# demeter_v28-TSSOP.net
KiCad netlist of a schematic drawn in EAGLE
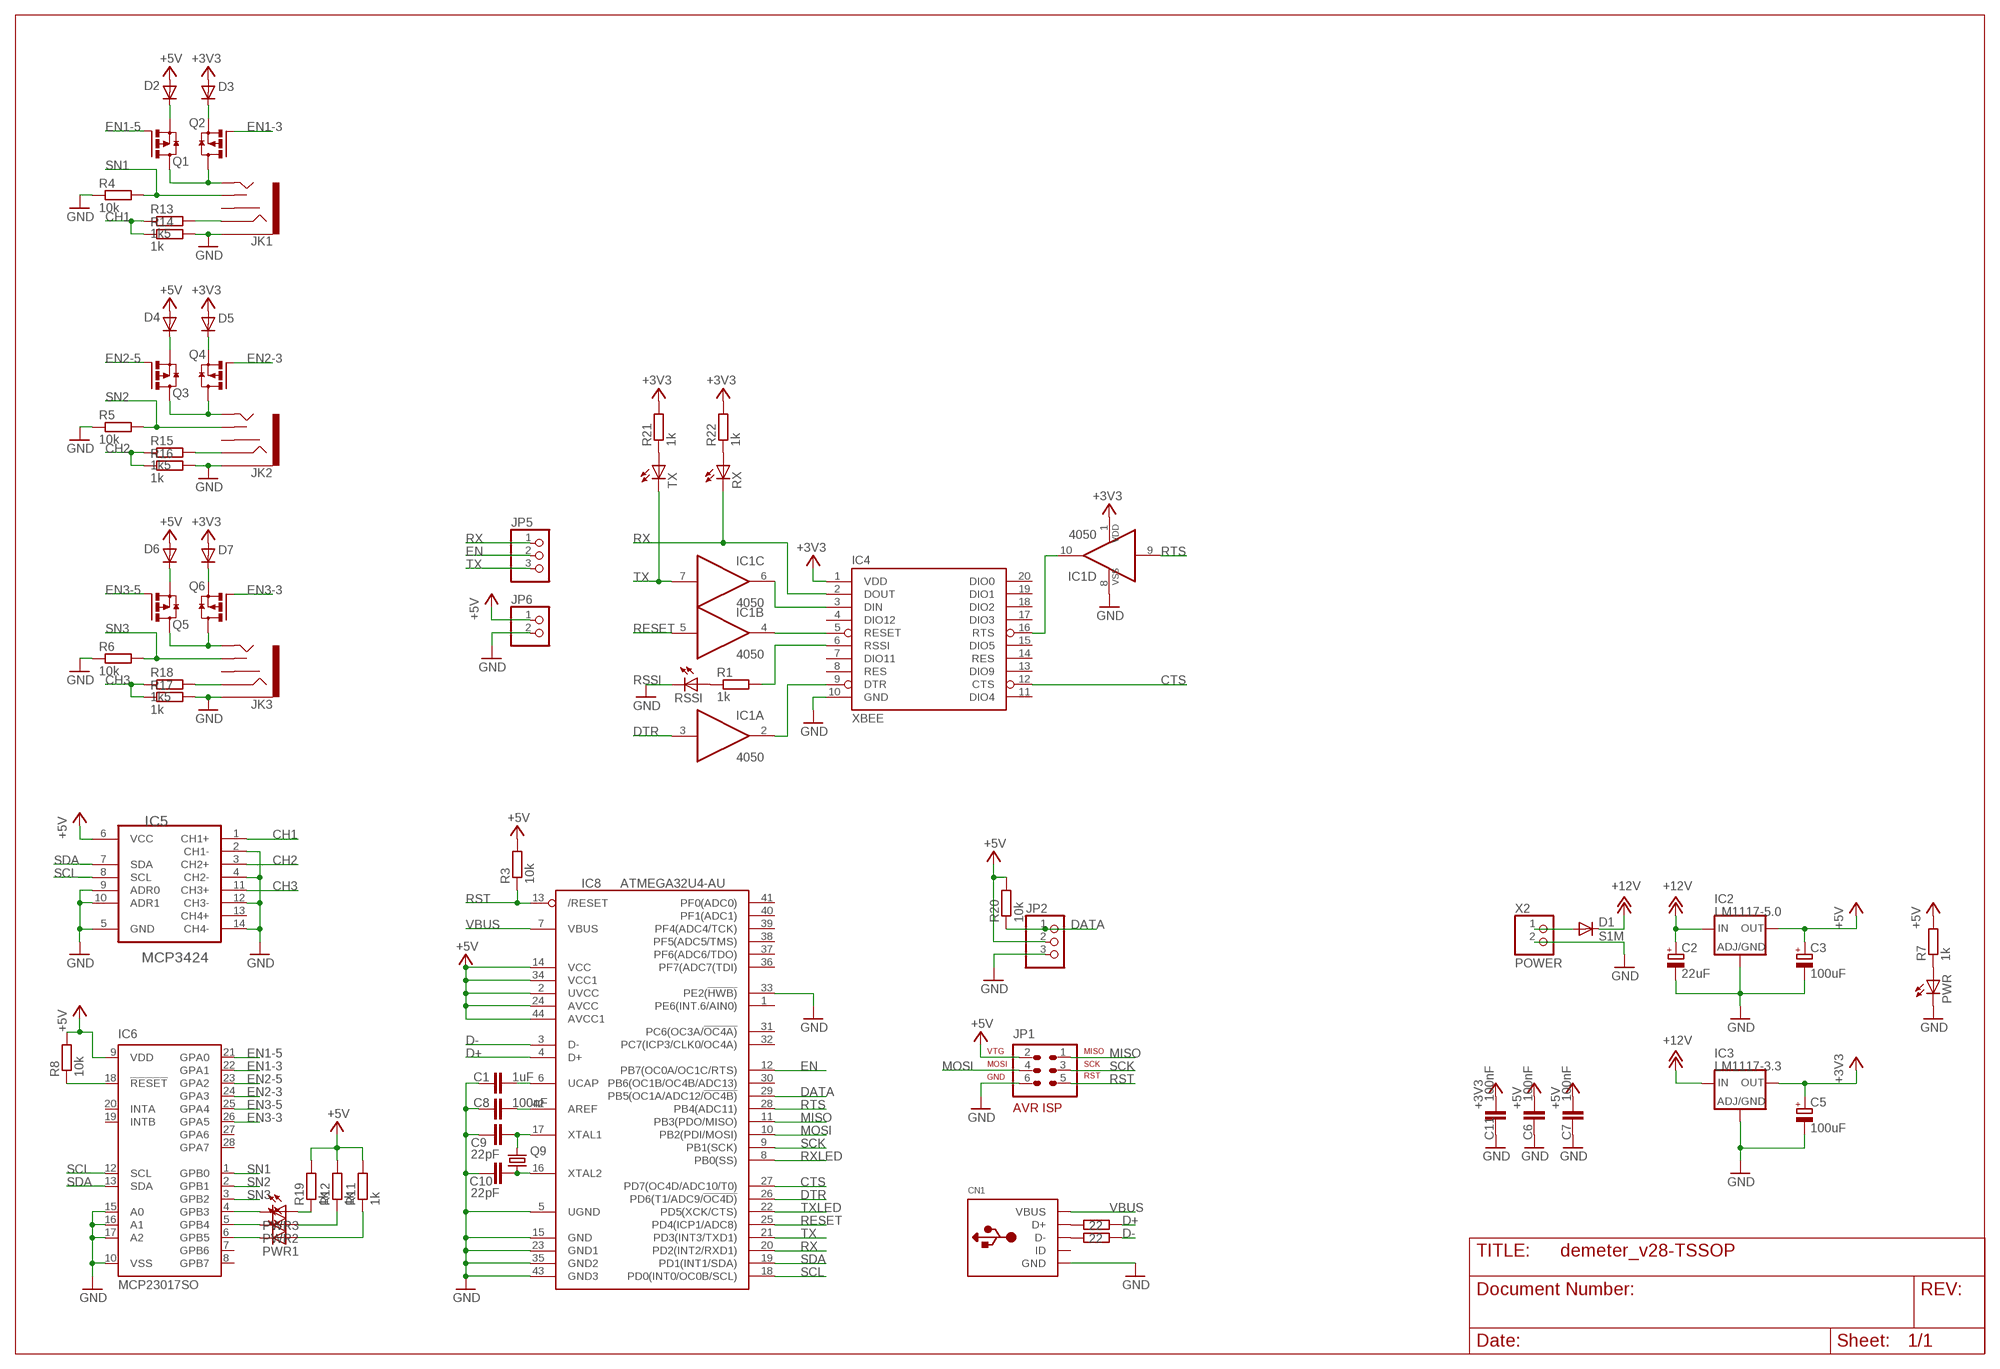
[diagram p0: schematic, sheet 1]

(export (version "E")
  (design (tool "Eeschema 10.0.6"))
  (components
    (comp (ref "C1")
      (value "1uF")
      (footprint "eagle-import:C0805K")
      (libsource (lib "eagle-import") (part "C-EUC0805K"))
    )
    (comp (ref "C2")
      (value "22uF")
      (footprint "eagle-import:PANASONIC_D")
      (libsource (lib "eagle-import") (part "CPOL-EUPD"))
    )
    (comp (ref "C3")
      (value "100uF")
      (footprint "eagle-import:PANASONIC_D")
      (libsource (lib "eagle-import") (part "CPOL-EUPD"))
    )
    (comp (ref "C5")
      (value "100uF")
      (footprint "eagle-import:PANASONIC_D")
      (libsource (lib "eagle-import") (part "CPOL-EUPD"))
    )
    (comp (ref "C6")
      (value "100nF")
      (footprint "eagle-import:C0805K")
      (libsource (lib "eagle-import") (part "C-EUC0805K"))
    )
    (comp (ref "C7")
      (value "100nF")
      (footprint "eagle-import:C0805K")
      (libsource (lib "eagle-import") (part "C-EUC0805K"))
    )
    (comp (ref "C8")
      (value "100nF")
      (footprint "eagle-import:C0805K")
      (libsource (lib "eagle-import") (part "C-EUC0805K"))
    )
    (comp (ref "C9")
      (value "22pF")
      (footprint "eagle-import:C0805K")
      (libsource (lib "eagle-import") (part "C-EUC0805K"))
    )
    (comp (ref "C10")
      (value "22pF")
      (footprint "eagle-import:C0805K")
      (libsource (lib "eagle-import") (part "C-EUC0805K"))
    )
    (comp (ref "C11")
      (value "100nF")
      (footprint "eagle-import:C0805K")
      (libsource (lib "eagle-import") (part "C-EUC0805K"))
    )
    (comp (ref "CN1")
      (value "USBMINIB")
      (footprint "eagle-import:USB-MINIB")
      (libsource (lib "eagle-import") (part "USBMINIB"))
    )
    (comp (ref "D1")
      (value "S1M")
      (footprint "eagle-import:DO-214AC")
      (libsource (lib "eagle-import") (part "S1M"))
    )
    (comp (ref "D2")
      (value "MBR0520")
      (footprint "eagle-import:SOD123")
      (libsource (lib "eagle-import") (part "MBR0520"))
    )
    (comp (ref "D3")
      (value "MBR0520")
      (footprint "eagle-import:SOD123")
      (libsource (lib "eagle-import") (part "MBR0520"))
    )
    (comp (ref "D4")
      (value "MBR0520")
      (footprint "eagle-import:SOD123")
      (libsource (lib "eagle-import") (part "MBR0520"))
    )
    (comp (ref "D5")
      (value "MBR0520")
      (footprint "eagle-import:SOD123")
      (libsource (lib "eagle-import") (part "MBR0520"))
    )
    (comp (ref "D6")
      (value "MBR0520")
      (footprint "eagle-import:SOD123")
      (libsource (lib "eagle-import") (part "MBR0520"))
    )
    (comp (ref "D7")
      (value "MBR0520")
      (footprint "eagle-import:SOD123")
      (libsource (lib "eagle-import") (part "MBR0520"))
    )
    (comp (ref "IC1")
      (value "4050")
      (footprint "eagle-import:SO16")
      (libsource (lib "eagle-import") (part "4050D"))
    )
    (comp (ref "IC2")
      (value "LM1117-5.0")
      (footprint "eagle-import:DPACK")
      (libsource (lib "eagle-import") (part "LM1117DT"))
    )
    (comp (ref "IC3")
      (value "LM1117-3.3")
      (footprint "eagle-import:DPACK")
      (libsource (lib "eagle-import") (part "LM1117DT"))
    )
    (comp (ref "IC4")
      (value "XBEE")
      (footprint "eagle-import:XBEE-1")
      (libsource (lib "eagle-import") (part "XBEE-1B1"))
    )
    (comp (ref "IC5")
      (value "MCP3424")
      (footprint "eagle-import:TSSOP14")
      (libsource (lib "eagle-import") (part "MCP3424T"))
    )
    (comp (ref "IC6")
      (value "MCP23017SO")
      (footprint "eagle-import:SO28W")
      (fields (field (name "MF") "MICROCHIP") (field (name "MPN") "MCP23017-E/SO"))
      (libsource (lib "eagle-import") (part "MCP23017SO"))
    )
    (comp (ref "IC8")
      (value "ATMEGA32U4-AU")
      (footprint "eagle-import:TQFP44")
      (libsource (lib "eagle-import") (part "ATMEGA32U4-AU"))
    )
    (comp (ref "JK1")
      (value "AUDIO-JACK2PTH")
      (footprint "eagle-import:AUDIO-JACK")
      (libsource (lib "eagle-import") (part "AUDIO-JACK2PTH"))
    )
    (comp (ref "JK2")
      (value "AUDIO-JACK2PTH")
      (footprint "eagle-import:AUDIO-JACK")
      (libsource (lib "eagle-import") (part "AUDIO-JACK2PTH"))
    )
    (comp (ref "JK3")
      (value "AUDIO-JACK2PTH")
      (footprint "eagle-import:AUDIO-JACK")
      (libsource (lib "eagle-import") (part "AUDIO-JACK2PTH"))
    )
    (comp (ref "JP1")
      (value "AVR-ISP")
      (footprint "eagle-import:AVR-ISP-6")
      (libsource (lib "eagle-import") (part "AVR-ISP-6"))
    )
    (comp (ref "JP2")
      (value "PINHD-1X3180")
      (footprint "eagle-import:1X03")
      (libsource (lib "eagle-import") (part "PINHD-1X3180"))
    )
    (comp (ref "JP5")
      (value "PINHD-1X3180")
      (footprint "eagle-import:1X03")
      (libsource (lib "eagle-import") (part "PINHD-1X3180"))
    )
    (comp (ref "JP6")
      (value "PINHD-1X2")
      (footprint "eagle-import:1X02")
      (libsource (lib "eagle-import") (part "PINHD-1X2"))
    )
    (comp (ref "PWR")
      (value "LED0805")
      (footprint "eagle-import:CHIP-LED0805")
      (libsource (lib "eagle-import") (part "LED0805"))
    )
    (comp (ref "PWR1")
      (value "LED0805")
      (footprint "eagle-import:CHIP-LED0805")
      (libsource (lib "eagle-import") (part "LED0805"))
    )
    (comp (ref "PWR2")
      (value "LED0805")
      (footprint "eagle-import:CHIP-LED0805")
      (libsource (lib "eagle-import") (part "LED0805"))
    )
    (comp (ref "PWR3")
      (value "LED0805")
      (footprint "eagle-import:CHIP-LED0805")
      (libsource (lib "eagle-import") (part "LED0805"))
    )
    (comp (ref "Q1")
      (value "IRLML6402")
      (footprint "eagle-import:SOT23")
      (libsource (lib "eagle-import") (part "IRLML6402"))
    )
    (comp (ref "Q2")
      (value "IRLML6402")
      (footprint "eagle-import:SOT23")
      (libsource (lib "eagle-import") (part "IRLML6402"))
    )
    (comp (ref "Q3")
      (value "IRLML6402")
      (footprint "eagle-import:SOT23")
      (libsource (lib "eagle-import") (part "IRLML6402"))
    )
    (comp (ref "Q4")
      (value "IRLML6402")
      (footprint "eagle-import:SOT23")
      (libsource (lib "eagle-import") (part "IRLML6402"))
    )
    (comp (ref "Q5")
      (value "IRLML6402")
      (footprint "eagle-import:SOT23")
      (libsource (lib "eagle-import") (part "IRLML6402"))
    )
    (comp (ref "Q6")
      (value "IRLML6402")
      (footprint "eagle-import:SOT23")
      (libsource (lib "eagle-import") (part "IRLML6402"))
    )
    (comp (ref "Q9")
      (value "CRYSTALHC49UP")
      (footprint "eagle-import:HC49UP")
      (libsource (lib "eagle-import") (part "CRYSTALHC49UP"))
    )
    (comp (ref "R1")
      (value "1k")
      (footprint "eagle-import:R0805")
      (libsource (lib "eagle-import") (part "R-EU_R0805"))
    )
    (comp (ref "R3")
      (value "10k")
      (footprint "eagle-import:R0805")
      (libsource (lib "eagle-import") (part "R-EU_R0805"))
    )
    (comp (ref "R4")
      (value "10k")
      (footprint "eagle-import:R0805")
      (libsource (lib "eagle-import") (part "R-EU_R0805"))
    )
    (comp (ref "R5")
      (value "10k")
      (footprint "eagle-import:R0805")
      (libsource (lib "eagle-import") (part "R-EU_R0805"))
    )
    (comp (ref "R6")
      (value "10k")
      (footprint "eagle-import:R0805")
      (libsource (lib "eagle-import") (part "R-EU_R0805"))
    )
    (comp (ref "R7")
      (value "1k")
      (footprint "eagle-import:R0805")
      (libsource (lib "eagle-import") (part "R-EU_R0805"))
    )
    (comp (ref "R8")
      (value "10k")
      (footprint "eagle-import:R0805")
      (libsource (lib "eagle-import") (part "R-EU_R0805"))
    )
    (comp (ref "R9")
      (value "22")
      (footprint "eagle-import:R0805")
      (libsource (lib "eagle-import") (part "R-EU_R0805"))
    )
    (comp (ref "R10")
      (value "22")
      (footprint "eagle-import:R0805")
      (libsource (lib "eagle-import") (part "R-EU_R0805"))
    )
    (comp (ref "R11")
      (value "1k")
      (footprint "eagle-import:R0805")
      (libsource (lib "eagle-import") (part "R-EU_R0805"))
    )
    (comp (ref "R12")
      (value "1k")
      (footprint "eagle-import:R0805")
      (libsource (lib "eagle-import") (part "R-EU_R0805"))
    )
    (comp (ref "R13")
      (value "1k5")
      (footprint "eagle-import:R0805")
      (libsource (lib "eagle-import") (part "R-EU_R0805"))
    )
    (comp (ref "R14")
      (value "1k")
      (footprint "eagle-import:R0805")
      (libsource (lib "eagle-import") (part "R-EU_R0805"))
    )
    (comp (ref "R15")
      (value "1k5")
      (footprint "eagle-import:R0805")
      (libsource (lib "eagle-import") (part "R-EU_R0805"))
    )
    (comp (ref "R16")
      (value "1k")
      (footprint "eagle-import:R0805")
      (libsource (lib "eagle-import") (part "R-EU_R0805"))
    )
    (comp (ref "R17")
      (value "1k")
      (footprint "eagle-import:R0805")
      (libsource (lib "eagle-import") (part "R-EU_R0805"))
    )
    (comp (ref "R18")
      (value "1k5")
      (footprint "eagle-import:R0805")
      (libsource (lib "eagle-import") (part "R-EU_R0805"))
    )
    (comp (ref "R19")
      (value "1k")
      (footprint "eagle-import:R0805")
      (libsource (lib "eagle-import") (part "R-EU_R0805"))
    )
    (comp (ref "R20")
      (value "10k")
      (footprint "eagle-import:R0805")
      (libsource (lib "eagle-import") (part "R-EU_R0805"))
    )
    (comp (ref "R21")
      (value "1k")
      (footprint "eagle-import:R0805")
      (libsource (lib "eagle-import") (part "R-EU_R0805"))
    )
    (comp (ref "R22")
      (value "1k")
      (footprint "eagle-import:R0805")
      (libsource (lib "eagle-import") (part "R-EU_R0805"))
    )
    (comp (ref "RSSI")
      (value "LED0805")
      (footprint "eagle-import:CHIP-LED0805")
      (libsource (lib "eagle-import") (part "LED0805"))
    )
    (comp (ref "RX")
      (value "LED0805")
      (footprint "eagle-import:CHIP-LED0805")
      (libsource (lib "eagle-import") (part "LED0805"))
    )
    (comp (ref "TX")
      (value "LED0805")
      (footprint "eagle-import:CHIP-LED0805")
      (libsource (lib "eagle-import") (part "LED0805"))
    )
    (comp (ref "X2")
      (value "POWER")
      (footprint "eagle-import:W237-102")
      (libsource (lib "eagle-import") (part "W237-102"))
    )
  )
  (nets
    (net (code "1") (name "+3V3") (class "Default")
      (node (ref "C11") (pin "1") (pinfunction "1_1") (pintype "passive"))
      (node (ref "C5") (pin "+") (pinfunction "+_+") (pintype "passive"))
      (node (ref "D3") (pin "A") (pinfunction "A_A") (pintype "passive"))
      (node (ref "D5") (pin "A") (pinfunction "A_A") (pintype "passive"))
      (node (ref "D7") (pin "A") (pinfunction "A_A") (pintype "passive"))
      (node (ref "IC1") (pin "1") (pinfunction "VDD_1") (pintype "power_in"))
      (node (ref "IC3") (pin "4") (pinfunction "OUT_4") (pintype "passive"))
      (node (ref "IC4") (pin "1") (pinfunction "VDD_1") (pintype "power_in"))
      (node (ref "R21") (pin "2") (pinfunction "2_2") (pintype "passive"))
      (node (ref "R22") (pin "2") (pinfunction "2_2") (pintype "passive"))
    )
    (net (code "2") (name "+5V") (class "Default")
      (node (ref "C3") (pin "+") (pinfunction "+_+") (pintype "passive"))
      (node (ref "C6") (pin "1") (pinfunction "1_1") (pintype "passive"))
      (node (ref "C7") (pin "1") (pinfunction "1_1") (pintype "passive"))
      (node (ref "D2") (pin "A") (pinfunction "A_A") (pintype "passive"))
      (node (ref "D4") (pin "A") (pinfunction "A_A") (pintype "passive"))
      (node (ref "D6") (pin "A") (pinfunction "A_A") (pintype "passive"))
      (node (ref "IC2") (pin "4") (pinfunction "OUT_4") (pintype "passive"))
      (node (ref "IC5") (pin "6") (pinfunction "VCC_6") (pintype "power_in"))
      (node (ref "IC6") (pin "9") (pinfunction "VDD_9") (pintype "power_in"))
      (node (ref "IC8") (pin "14") (pinfunction "VCC_14") (pintype "bidirectional"))
      (node (ref "IC8") (pin "2") (pinfunction "UVCC_2") (pintype "bidirectional"))
      (node (ref "IC8") (pin "24") (pinfunction "AVCC_24") (pintype "bidirectional"))
      (node (ref "IC8") (pin "34") (pinfunction "VCC1_34") (pintype "bidirectional"))
      (node (ref "IC8") (pin "44") (pinfunction "AVCC1_44") (pintype "bidirectional"))
      (node (ref "JP1") (pin "2") (pinfunction "VTG_2") (pintype "passive"))
      (node (ref "JP2") (pin "2") (pinfunction "2_2") (pintype "passive"))
      (node (ref "JP6") (pin "1") (pinfunction "1_1") (pintype "passive"))
      (node (ref "R11") (pin "2") (pinfunction "2_2") (pintype "passive"))
      (node (ref "R12") (pin "2") (pinfunction "2_2") (pintype "passive"))
      (node (ref "R19") (pin "2") (pinfunction "2_2") (pintype "passive"))
      (node (ref "R20") (pin "2") (pinfunction "2_2") (pintype "passive"))
      (node (ref "R3") (pin "2") (pinfunction "2_2") (pintype "passive"))
      (node (ref "R7") (pin "2") (pinfunction "2_2") (pintype "passive"))
      (node (ref "R8") (pin "2") (pinfunction "2_2") (pintype "passive"))
    )
    (net (code "3") (name "+12V") (class "Default")
      (node (ref "C2") (pin "+") (pinfunction "+_+") (pintype "passive"))
      (node (ref "D1") (pin "C") (pinfunction "C_C") (pintype "passive"))
      (node (ref "IC2") (pin "3") (pinfunction "IN_3") (pintype "input"))
      (node (ref "IC3") (pin "3") (pinfunction "IN_3") (pintype "input"))
    )
    (net (code "4") (name "/CH1") (class "Default")
      (node (ref "IC5") (pin "1") (pinfunction "CH1+_1") (pintype "input"))
      (node (ref "R13") (pin "1") (pinfunction "1_1") (pintype "passive"))
      (node (ref "R14") (pin "1") (pinfunction "1_1") (pintype "passive"))
    )
    (net (code "5") (name "/CH2") (class "Default")
      (node (ref "IC5") (pin "3") (pinfunction "CH2+_3") (pintype "input"))
      (node (ref "R15") (pin "1") (pinfunction "1_1") (pintype "passive"))
      (node (ref "R16") (pin "1") (pinfunction "1_1") (pintype "passive"))
    )
    (net (code "6") (name "/CH3") (class "Default")
      (node (ref "IC5") (pin "11") (pinfunction "CH3+_11") (pintype "input"))
      (node (ref "R17") (pin "1") (pinfunction "1_1") (pintype "passive"))
      (node (ref "R18") (pin "1") (pinfunction "1_1") (pintype "passive"))
    )
    (net (code "7") (name "/CTS") (class "Default")
      (node (ref "IC4") (pin "12") (pinfunction "CTS_12") (pintype "output"))
      (node (ref "IC8") (pin "27") (pinfunction "PD7(OC4D/ADC10/T0)_27") (pintype "bidirectional"))
    )
    (net (code "8") (name "/D+") (class "Default")
      (node (ref "IC8") (pin "4") (pinfunction "D+_4") (pintype "bidirectional"))
      (node (ref "R9") (pin "1") (pinfunction "1_1") (pintype "passive"))
    )
    (net (code "9") (name "/D-") (class "Default")
      (node (ref "IC8") (pin "3") (pinfunction "D-_3") (pintype "bidirectional"))
      (node (ref "R10") (pin "1") (pinfunction "1_1") (pintype "passive"))
    )
    (net (code "10") (name "/DATA") (class "Default")
      (node (ref "IC8") (pin "29") (pinfunction "PB5(OC1A/ADC12/~{OC4B})_29") (pintype "bidirectional"))
      (node (ref "JP2") (pin "1") (pinfunction "1_1") (pintype "passive"))
      (node (ref "R20") (pin "1") (pinfunction "1_1") (pintype "passive"))
    )
    (net (code "11") (name "/DTR") (class "Default")
      (node (ref "IC1") (pin "3") (pinfunction "I_3") (pintype "input"))
      (node (ref "IC8") (pin "26") (pinfunction "PD6(T1/ADC9/~{OC4D})_26") (pintype "bidirectional"))
    )
    (net (code "12") (name "/EN") (class "Default")
      (node (ref "IC8") (pin "12") (pinfunction "PB7(OC0A/OC1C/RTS)_12") (pintype "bidirectional"))
      (node (ref "JP5") (pin "2") (pinfunction "2_2") (pintype "passive"))
    )
    (net (code "13") (name "/EN1-3") (class "Default")
      (node (ref "IC6") (pin "22") (pinfunction "GPA1_22") (pintype "bidirectional"))
      (node (ref "Q2") (pin "1") (pinfunction "G_1") (pintype "passive"))
    )
    (net (code "14") (name "/EN1-5") (class "Default")
      (node (ref "IC6") (pin "21") (pinfunction "GPA0_21") (pintype "bidirectional"))
      (node (ref "Q1") (pin "1") (pinfunction "G_1") (pintype "passive"))
    )
    (net (code "15") (name "/EN2-3") (class "Default")
      (node (ref "IC6") (pin "24") (pinfunction "GPA3_24") (pintype "bidirectional"))
      (node (ref "Q4") (pin "1") (pinfunction "G_1") (pintype "passive"))
    )
    (net (code "16") (name "/EN2-5") (class "Default")
      (node (ref "IC6") (pin "23") (pinfunction "GPA2_23") (pintype "bidirectional"))
      (node (ref "Q3") (pin "1") (pinfunction "G_1") (pintype "passive"))
    )
    (net (code "17") (name "/EN3-3") (class "Default")
      (node (ref "IC6") (pin "26") (pinfunction "GPA5_26") (pintype "bidirectional"))
      (node (ref "Q6") (pin "1") (pinfunction "G_1") (pintype "passive"))
    )
    (net (code "18") (name "/EN3-5") (class "Default")
      (node (ref "IC6") (pin "25") (pinfunction "GPA4_25") (pintype "bidirectional"))
      (node (ref "Q5") (pin "1") (pinfunction "G_1") (pintype "passive"))
    )
    (net (code "19") (name "/MISO") (class "Default")
      (node (ref "IC8") (pin "11") (pinfunction "PB3(PDO/MISO)_11") (pintype "bidirectional"))
      (node (ref "JP1") (pin "1") (pinfunction "MISO_1") (pintype "passive"))
    )
    (net (code "20") (name "/MOSI") (class "Default")
      (node (ref "IC8") (pin "10") (pinfunction "PB2(PDI/MOSI)_10") (pintype "bidirectional"))
      (node (ref "JP1") (pin "4") (pinfunction "MOSI_4") (pintype "passive"))
    )
    (net (code "21") (name "/RESET") (class "Default")
      (node (ref "IC1") (pin "5") (pinfunction "I_5") (pintype "input"))
      (node (ref "IC8") (pin "25") (pinfunction "PD4(ICP1/ADC8)_25") (pintype "bidirectional"))
    )
    (net (code "22") (name "/RSSI") (class "Default")
      (node (ref "IC4") (pin "6") (pinfunction "RSSI_6") (pintype "bidirectional"))
      (node (ref "R1") (pin "2") (pinfunction "2_2") (pintype "passive"))
    )
    (net (code "23") (name "/RST") (class "Default")
      (node (ref "IC8") (pin "13") (pinfunction "/RESET_13") (pintype "bidirectional"))
      (node (ref "JP1") (pin "5") (pinfunction "RST_5") (pintype "passive"))
      (node (ref "R3") (pin "1") (pinfunction "1_1") (pintype "passive"))
    )
    (net (code "24") (name "/RTS") (class "Default")
      (node (ref "IC1") (pin "9") (pinfunction "I_9") (pintype "input"))
      (node (ref "IC8") (pin "28") (pinfunction "PB4(ADC11)_28") (pintype "bidirectional"))
    )
    (net (code "25") (name "/RX") (class "Default")
      (node (ref "IC4") (pin "2") (pinfunction "DOUT_2") (pintype "output"))
      (node (ref "IC8") (pin "20") (pinfunction "PD2(INT2/RXD1)_20") (pintype "bidirectional"))
      (node (ref "JP5") (pin "1") (pinfunction "1_1") (pintype "passive"))
      (node (ref "RX") (pin "C") (pinfunction "C_C") (pintype "passive"))
    )
    (net (code "26") (name "/RXLED") (class "Default")
      (node (ref "IC8") (pin "8") (pinfunction "PB0(SS)_8") (pintype "bidirectional"))
    )
    (net (code "27") (name "/SCK") (class "Default")
      (node (ref "IC8") (pin "9") (pinfunction "PB1(SCK)_9") (pintype "bidirectional"))
      (node (ref "JP1") (pin "3") (pinfunction "SCK_3") (pintype "passive"))
    )
    (net (code "28") (name "/SCL") (class "Default")
      (node (ref "IC5") (pin "8") (pinfunction "SCL_8") (pintype "input"))
      (node (ref "IC6") (pin "12") (pinfunction "SCL_12") (pintype "input"))
      (node (ref "IC8") (pin "18") (pinfunction "PD0(INT0/OC0B/SCL)_18") (pintype "bidirectional"))
    )
    (net (code "29") (name "/SDA") (class "Default")
      (node (ref "IC5") (pin "7") (pinfunction "SDA_7") (pintype "bidirectional"))
      (node (ref "IC6") (pin "13") (pinfunction "SDA_13") (pintype "bidirectional"))
      (node (ref "IC8") (pin "19") (pinfunction "PD1(INT1/SDA)_19") (pintype "bidirectional"))
    )
    (net (code "30") (name "/SN1") (class "Default")
      (node (ref "IC6") (pin "1") (pinfunction "GPB0_1") (pintype "bidirectional"))
      (node (ref "JK1") (pin "TSH") (pinfunction "TSH_TSH") (pintype "bidirectional"))
      (node (ref "R4") (pin "2") (pinfunction "2_2") (pintype "passive"))
    )
    (net (code "31") (name "/SN2") (class "Default")
      (node (ref "IC6") (pin "2") (pinfunction "GPB1_2") (pintype "bidirectional"))
      (node (ref "JK2") (pin "TSH") (pinfunction "TSH_TSH") (pintype "bidirectional"))
      (node (ref "R5") (pin "2") (pinfunction "2_2") (pintype "passive"))
    )
    (net (code "32") (name "/SN3") (class "Default")
      (node (ref "IC6") (pin "3") (pinfunction "GPB2_3") (pintype "bidirectional"))
      (node (ref "JK3") (pin "TSH") (pinfunction "TSH_TSH") (pintype "bidirectional"))
      (node (ref "R6") (pin "2") (pinfunction "2_2") (pintype "passive"))
    )
    (net (code "33") (name "/TX") (class "Default")
      (node (ref "IC1") (pin "7") (pinfunction "I_7") (pintype "input"))
      (node (ref "IC8") (pin "21") (pinfunction "PD3(INT3/TXD1)_21") (pintype "bidirectional"))
      (node (ref "JP5") (pin "3") (pinfunction "3_3") (pintype "passive"))
      (node (ref "TX") (pin "C") (pinfunction "C_C") (pintype "passive"))
    )
    (net (code "34") (name "/TXLED") (class "Default")
      (node (ref "IC8") (pin "22") (pinfunction "PD5(XCK/CTS)_22") (pintype "bidirectional"))
    )
    (net (code "35") (name "/VBUS") (class "Default")
      (node (ref "CN1") (pin "VBUS") (pinfunction "VBUS_VBUS") (pintype "power_in"))
      (node (ref "IC8") (pin "7") (pinfunction "VBUS_7") (pintype "bidirectional"))
    )
    (net (code "36") (name "GND") (class "Default")
      (node (ref "C1") (pin "2") (pinfunction "2_2") (pintype "passive"))
      (node (ref "C10") (pin "2") (pinfunction "2_2") (pintype "passive"))
      (node (ref "C11") (pin "2") (pinfunction "2_2") (pintype "passive"))
      (node (ref "C2") (pin "-") (pinfunction "-_-") (pintype "passive"))
      (node (ref "C3") (pin "-") (pinfunction "-_-") (pintype "passive"))
      (node (ref "C5") (pin "-") (pinfunction "-_-") (pintype "passive"))
      (node (ref "C6") (pin "2") (pinfunction "2_2") (pintype "passive"))
      (node (ref "C7") (pin "2") (pinfunction "2_2") (pintype "passive"))
      (node (ref "C8") (pin "2") (pinfunction "2_2") (pintype "passive"))
      (node (ref "C9") (pin "2") (pinfunction "2_2") (pintype "passive"))
      (node (ref "CN1") (pin "GND") (pinfunction "GND_GND") (pintype "power_in"))
      (node (ref "CN1") (pin "GND1") (pinfunction "GND_GND1") (pintype "power_in"))
      (node (ref "CN1") (pin "GND2") (pinfunction "GND_GND2") (pintype "power_in"))
      (node (ref "CN1") (pin "GND3") (pinfunction "GND_GND3") (pintype "power_in"))
      (node (ref "CN1") (pin "GND4") (pinfunction "GND_GND4") (pintype "power_in"))
      (node (ref "IC1") (pin "8") (pinfunction "VSS_8") (pintype "power_in"))
      (node (ref "IC2") (pin "1") (pinfunction "ADJ_1") (pintype "input"))
      (node (ref "IC3") (pin "1") (pinfunction "ADJ_1") (pintype "input"))
      (node (ref "IC4") (pin "10") (pinfunction "GND_10") (pintype "power_in"))
      (node (ref "IC5") (pin "10") (pinfunction "ADR1_10") (pintype "input"))
      (node (ref "IC5") (pin "12") (pinfunction "CH3-_12") (pintype "input"))
      (node (ref "IC5") (pin "14") (pinfunction "CH4-_14") (pintype "input"))
      (node (ref "IC5") (pin "2") (pinfunction "CH1-_2") (pintype "input"))
      (node (ref "IC5") (pin "4") (pinfunction "CH2-_4") (pintype "input"))
      (node (ref "IC5") (pin "5") (pinfunction "GND_5") (pintype "power_in"))
      (node (ref "IC5") (pin "9") (pinfunction "ADR0_9") (pintype "input"))
      (node (ref "IC6") (pin "10") (pinfunction "VSS_10") (pintype "power_in"))
      (node (ref "IC6") (pin "15") (pinfunction "A0_15") (pintype "input"))
      (node (ref "IC6") (pin "16") (pinfunction "A1_16") (pintype "input"))
      (node (ref "IC6") (pin "17") (pinfunction "A2_17") (pintype "input"))
      (node (ref "IC8") (pin "15") (pinfunction "GND_15") (pintype "bidirectional"))
      (node (ref "IC8") (pin "23") (pinfunction "GND1_23") (pintype "bidirectional"))
      (node (ref "IC8") (pin "33") (pinfunction "PE2(~{HWB})_33") (pintype "bidirectional"))
      (node (ref "IC8") (pin "35") (pinfunction "GND2_35") (pintype "bidirectional"))
      (node (ref "IC8") (pin "43") (pinfunction "GND3_43") (pintype "bidirectional"))
      (node (ref "IC8") (pin "5") (pinfunction "UGND_5") (pintype "bidirectional"))
      (node (ref "JK1") (pin "SLEEVE") (pinfunction "SLEEVE_SLEEVE") (pintype "bidirectional"))
      (node (ref "JK2") (pin "SLEEVE") (pinfunction "SLEEVE_SLEEVE") (pintype "bidirectional"))
      (node (ref "JK3") (pin "SLEEVE") (pinfunction "SLEEVE_SLEEVE") (pintype "bidirectional"))
      (node (ref "JP1") (pin "6") (pinfunction "GND_6") (pintype "passive"))
      (node (ref "JP2") (pin "3") (pinfunction "3_3") (pintype "passive"))
      (node (ref "JP6") (pin "2") (pinfunction "2_2") (pintype "passive"))
      (node (ref "PWR") (pin "C") (pinfunction "C_C") (pintype "passive"))
      (node (ref "R14") (pin "2") (pinfunction "2_2") (pintype "passive"))
      (node (ref "R16") (pin "2") (pinfunction "2_2") (pintype "passive"))
      (node (ref "R17") (pin "2") (pinfunction "2_2") (pintype "passive"))
      (node (ref "R4") (pin "1") (pinfunction "1_1") (pintype "passive"))
      (node (ref "R5") (pin "1") (pinfunction "1_1") (pintype "passive"))
      (node (ref "R6") (pin "1") (pinfunction "1_1") (pintype "passive"))
      (node (ref "RSSI") (pin "C") (pinfunction "C_C") (pintype "passive"))
      (node (ref "X2") (pin "2") (pinfunction "2_2") (pintype "passive"))
    )
    (net (code "37") (name "Net-(CN1-PadD+)") (class "Default")
      (node (ref "CN1") (pin "D+") (pinfunction "D+_D+") (pintype "bidirectional"))
      (node (ref "R9") (pin "2") (pinfunction "2_2") (pintype "passive"))
    )
    (net (code "38") (name "Net-(CN1-PadD-)") (class "Default")
      (node (ref "CN1") (pin "D-") (pinfunction "D-_D-") (pintype "bidirectional"))
      (node (ref "R10") (pin "2") (pinfunction "2_2") (pintype "passive"))
    )
    (net (code "39") (name "Net-(D1-PadA)") (class "Default")
      (node (ref "D1") (pin "A") (pinfunction "A_A") (pintype "passive"))
      (node (ref "X2") (pin "1") (pinfunction "1_1") (pintype "passive"))
    )
    (net (code "40") (name "Net-(IC1A-O)") (class "Default")
      (node (ref "IC1") (pin "2") (pinfunction "O_2") (pintype "output"))
      (node (ref "IC4") (pin "9") (pinfunction "DTR_9") (pintype "bidirectional"))
    )
    (net (code "41") (name "Net-(IC1B-O)") (class "Default")
      (node (ref "IC1") (pin "4") (pinfunction "O_4") (pintype "output"))
      (node (ref "IC4") (pin "5") (pinfunction "RESET_5") (pintype "input"))
    )
    (net (code "42") (name "Net-(IC1C-O)") (class "Default")
      (node (ref "IC1") (pin "6") (pinfunction "O_6") (pintype "output"))
      (node (ref "IC4") (pin "3") (pinfunction "DIN_3") (pintype "input"))
    )
    (net (code "43") (name "Net-(IC1D-O)") (class "Default")
      (node (ref "IC1") (pin "10") (pinfunction "O_10") (pintype "output"))
      (node (ref "IC4") (pin "16") (pinfunction "RTS_16") (pintype "input"))
    )
    (net (code "44") (name "Net-(IC6-GPB3)") (class "Default")
      (node (ref "IC6") (pin "4") (pinfunction "GPB3_4") (pintype "bidirectional"))
      (node (ref "PWR3") (pin "C") (pinfunction "C_C") (pintype "passive"))
    )
    (net (code "45") (name "Net-(IC6-GPB4)") (class "Default")
      (node (ref "IC6") (pin "5") (pinfunction "GPB4_5") (pintype "bidirectional"))
      (node (ref "PWR2") (pin "C") (pinfunction "C_C") (pintype "passive"))
    )
    (net (code "46") (name "Net-(IC6-GPB5)") (class "Default")
      (node (ref "IC6") (pin "6") (pinfunction "GPB5_6") (pintype "bidirectional"))
      (node (ref "PWR1") (pin "C") (pinfunction "C_C") (pintype "passive"))
    )
    (net (code "47") (name "Net-(IC6-~{RESET})") (class "Default")
      (node (ref "IC6") (pin "18") (pinfunction "~{RESET}_18") (pintype "input"))
      (node (ref "R8") (pin "1") (pinfunction "1_1") (pintype "passive"))
    )
    (net (code "48") (name "Net-(IC8-AREF)") (class "Default")
      (node (ref "C8") (pin "1") (pinfunction "1_1") (pintype "passive"))
      (node (ref "IC8") (pin "42") (pinfunction "AREF_42") (pintype "bidirectional"))
    )
    (net (code "49") (name "Net-(IC8-UCAP)") (class "Default")
      (node (ref "C1") (pin "1") (pinfunction "1_1") (pintype "passive"))
      (node (ref "IC8") (pin "6") (pinfunction "UCAP_6") (pintype "bidirectional"))
    )
    (net (code "50") (name "Net-(IC8-XTAL1)") (class "Default")
      (node (ref "C9") (pin "1") (pinfunction "1_1") (pintype "passive"))
      (node (ref "IC8") (pin "17") (pinfunction "XTAL1_17") (pintype "bidirectional"))
      (node (ref "Q9") (pin "2") (pinfunction "2_2") (pintype "passive"))
    )
    (net (code "51") (name "Net-(IC8-XTAL2)") (class "Default")
      (node (ref "C10") (pin "1") (pinfunction "1_1") (pintype "passive"))
      (node (ref "IC8") (pin "16") (pinfunction "XTAL2_16") (pintype "bidirectional"))
      (node (ref "Q9") (pin "1") (pinfunction "1_1") (pintype "passive"))
    )
    (net (code "52") (name "Net-(JK1-PadRING)") (class "Default")
      (node (ref "JK1") (pin "RING") (pinfunction "RING_RING") (pintype "bidirectional"))
      (node (ref "R13") (pin "2") (pinfunction "2_2") (pintype "passive"))
    )
    (net (code "53") (name "Net-(JK2-PadRING)") (class "Default")
      (node (ref "JK2") (pin "RING") (pinfunction "RING_RING") (pintype "bidirectional"))
      (node (ref "R15") (pin "2") (pinfunction "2_2") (pintype "passive"))
    )
    (net (code "54") (name "Net-(JK3-PadRING)") (class "Default")
      (node (ref "JK3") (pin "RING") (pinfunction "RING_RING") (pintype "bidirectional"))
      (node (ref "R18") (pin "2") (pinfunction "2_2") (pintype "passive"))
    )
    (net (code "55") (name "Net-(PWR-PadA)") (class "Default")
      (node (ref "PWR") (pin "A") (pinfunction "A_A") (pintype "passive"))
      (node (ref "R7") (pin "1") (pinfunction "1_1") (pintype "passive"))
    )
    (net (code "56") (name "Net-(PWR1-PadA)") (class "Default")
      (node (ref "PWR1") (pin "A") (pinfunction "A_A") (pintype "passive"))
      (node (ref "R11") (pin "1") (pinfunction "1_1") (pintype "passive"))
    )
    (net (code "57") (name "Net-(PWR2-PadA)") (class "Default")
      (node (ref "PWR2") (pin "A") (pinfunction "A_A") (pintype "passive"))
      (node (ref "R12") (pin "1") (pinfunction "1_1") (pintype "passive"))
    )
    (net (code "58") (name "Net-(PWR3-PadA)") (class "Default")
      (node (ref "PWR3") (pin "A") (pinfunction "A_A") (pintype "passive"))
      (node (ref "R19") (pin "1") (pinfunction "1_1") (pintype "passive"))
    )
    (net (code "59") (name "Net-(Q1-D)") (class "Default")
      (node (ref "JK1") (pin "TIP") (pinfunction "TIP_TIP") (pintype "bidirectional"))
      (node (ref "Q1") (pin "3") (pinfunction "D_3") (pintype "passive"))
      (node (ref "Q2") (pin "3") (pinfunction "D_3") (pintype "passive"))
    )
    (net (code "60") (name "Net-(Q1-S)") (class "Default")
      (node (ref "D2") (pin "C") (pinfunction "C_C") (pintype "passive"))
      (node (ref "Q1") (pin "2") (pinfunction "S_2") (pintype "passive"))
    )
    (net (code "61") (name "Net-(Q2-S)") (class "Default")
      (node (ref "D3") (pin "C") (pinfunction "C_C") (pintype "passive"))
      (node (ref "Q2") (pin "2") (pinfunction "S_2") (pintype "passive"))
    )
    (net (code "62") (name "Net-(Q3-D)") (class "Default")
      (node (ref "JK2") (pin "TIP") (pinfunction "TIP_TIP") (pintype "bidirectional"))
      (node (ref "Q3") (pin "3") (pinfunction "D_3") (pintype "passive"))
      (node (ref "Q4") (pin "3") (pinfunction "D_3") (pintype "passive"))
    )
    (net (code "63") (name "Net-(Q3-S)") (class "Default")
      (node (ref "D4") (pin "C") (pinfunction "C_C") (pintype "passive"))
      (node (ref "Q3") (pin "2") (pinfunction "S_2") (pintype "passive"))
    )
    (net (code "64") (name "Net-(Q4-S)") (class "Default")
      (node (ref "D5") (pin "C") (pinfunction "C_C") (pintype "passive"))
      (node (ref "Q4") (pin "2") (pinfunction "S_2") (pintype "passive"))
    )
    (net (code "65") (name "Net-(Q5-D)") (class "Default")
      (node (ref "JK3") (pin "TIP") (pinfunction "TIP_TIP") (pintype "bidirectional"))
      (node (ref "Q5") (pin "3") (pinfunction "D_3") (pintype "passive"))
      (node (ref "Q6") (pin "3") (pinfunction "D_3") (pintype "passive"))
    )
    (net (code "66") (name "Net-(Q5-S)") (class "Default")
      (node (ref "D6") (pin "C") (pinfunction "C_C") (pintype "passive"))
      (node (ref "Q5") (pin "2") (pinfunction "S_2") (pintype "passive"))
    )
    (net (code "67") (name "Net-(Q6-S)") (class "Default")
      (node (ref "D7") (pin "C") (pinfunction "C_C") (pintype "passive"))
      (node (ref "Q6") (pin "2") (pinfunction "S_2") (pintype "passive"))
    )
    (net (code "68") (name "Net-(R1-Pad1)") (class "Default")
      (node (ref "R1") (pin "1") (pinfunction "1_1") (pintype "passive"))
      (node (ref "RSSI") (pin "A") (pinfunction "A_A") (pintype "passive"))
    )
    (net (code "69") (name "Net-(R21-Pad1)") (class "Default")
      (node (ref "R21") (pin "1") (pinfunction "1_1") (pintype "passive"))
      (node (ref "TX") (pin "A") (pinfunction "A_A") (pintype "passive"))
    )
    (net (code "70") (name "Net-(R22-Pad1)") (class "Default")
      (node (ref "R22") (pin "1") (pinfunction "1_1") (pintype "passive"))
      (node (ref "RX") (pin "A") (pinfunction "A_A") (pintype "passive"))
    )
    (net (code "71") (name "unconnected-(CN1-PadID)") (class "Default")
      (node (ref "CN1") (pin "ID") (pinfunction "ID_ID") (pintype "bidirectional"))
    )
    (net (code "72") (name "unconnected-(IC4-DIO0-Pad20)") (class "Default")
      (node (ref "IC4") (pin "20") (pinfunction "DIO0_20") (pintype "bidirectional"))
    )
    (net (code "73") (name "unconnected-(IC4-DIO1-Pad19)") (class "Default")
      (node (ref "IC4") (pin "19") (pinfunction "DIO1_19") (pintype "bidirectional"))
    )
    (net (code "74") (name "unconnected-(IC4-DIO2-Pad18)") (class "Default")
      (node (ref "IC4") (pin "18") (pinfunction "DIO2_18") (pintype "bidirectional"))
    )
    (net (code "75") (name "unconnected-(IC4-DIO3-Pad17)") (class "Default")
      (node (ref "IC4") (pin "17") (pinfunction "DIO3_17") (pintype "bidirectional"))
    )
    (net (code "76") (name "unconnected-(IC4-DIO4-Pad11)") (class "Default")
      (node (ref "IC4") (pin "11") (pinfunction "DIO4_11") (pintype "bidirectional"))
    )
    (net (code "77") (name "unconnected-(IC4-DIO5-Pad15)") (class "Default")
      (node (ref "IC4") (pin "15") (pinfunction "DIO5_15") (pintype "bidirectional"))
    )
    (net (code "78") (name "unconnected-(IC4-DIO9-Pad13)") (class "Default")
      (node (ref "IC4") (pin "13") (pinfunction "DIO9_13") (pintype "bidirectional"))
    )
    (net (code "79") (name "unconnected-(IC4-DIO11-Pad7)") (class "Default")
      (node (ref "IC4") (pin "7") (pinfunction "DIO11_7") (pintype "bidirectional"))
    )
    (net (code "80") (name "unconnected-(IC4-DIO12-Pad4)") (class "Default")
      (node (ref "IC4") (pin "4") (pinfunction "DIO12_4") (pintype "bidirectional"))
    )
    (net (code "81") (name "unconnected-(IC4-RES-Pad8)") (class "Default")
      (node (ref "IC4") (pin "8") (pinfunction "RES_8") (pintype "bidirectional"))
    )
    (net (code "82") (name "unconnected-(IC4-RES-Pad14)") (class "Default")
      (node (ref "IC4") (pin "14") (pinfunction "RES_14") (pintype "bidirectional"))
    )
    (net (code "83") (name "unconnected-(IC5-CH4+-Pad13)") (class "Default")
      (node (ref "IC5") (pin "13") (pinfunction "CH4+_13") (pintype "input"))
    )
    (net (code "84") (name "unconnected-(IC6-GPA6-Pad27)") (class "Default")
      (node (ref "IC6") (pin "27") (pinfunction "GPA6_27") (pintype "bidirectional"))
    )
    (net (code "85") (name "unconnected-(IC6-GPA7-Pad28)") (class "Default")
      (node (ref "IC6") (pin "28") (pinfunction "GPA7_28") (pintype "bidirectional"))
    )
    (net (code "86") (name "unconnected-(IC6-GPB6-Pad7)") (class "Default")
      (node (ref "IC6") (pin "7") (pinfunction "GPB6_7") (pintype "bidirectional"))
    )
    (net (code "87") (name "unconnected-(IC6-GPB7-Pad8)") (class "Default")
      (node (ref "IC6") (pin "8") (pinfunction "GPB7_8") (pintype "bidirectional"))
    )
    (net (code "88") (name "unconnected-(IC6-INTA-Pad20)") (class "Default")
      (node (ref "IC6") (pin "20") (pinfunction "INTA_20") (pintype "output"))
    )
    (net (code "89") (name "unconnected-(IC6-INTB-Pad19)") (class "Default")
      (node (ref "IC6") (pin "19") (pinfunction "INTB_19") (pintype "output"))
    )
    (net (code "90") (name "unconnected-(IC8-PB6(OC1B{slash}OC4B{slash}ADC13)-Pad30)") (class "Default")
      (node (ref "IC8") (pin "30") (pinfunction "PB6(OC1B/OC4B/ADC13)_30") (pintype "bidirectional"))
    )
    (net (code "91") (name "unconnected-(IC8-PC6(OC3A{slash}~{OC4A})-Pad31)") (class "Default")
      (node (ref "IC8") (pin "31") (pinfunction "PC6(OC3A/~{OC4A})_31") (pintype "bidirectional"))
    )
    (net (code "92") (name "unconnected-(IC8-PC7(ICP3{slash}CLK0{slash}OC4A)-Pad32)") (class "Default")
      (node (ref "IC8") (pin "32") (pinfunction "PC7(ICP3/CLK0/OC4A)_32") (pintype "bidirectional"))
    )
    (net (code "93") (name "unconnected-(IC8-PE6(INT.6{slash}AIN0)-Pad1)") (class "Default")
      (node (ref "IC8") (pin "1") (pinfunction "PE6(INT.6/AIN0)_1") (pintype "bidirectional"))
    )
    (net (code "94") (name "unconnected-(IC8-PF0(ADC0)-Pad41)") (class "Default")
      (node (ref "IC8") (pin "41") (pinfunction "PF0(ADC0)_41") (pintype "bidirectional"))
    )
    (net (code "95") (name "unconnected-(IC8-PF1(ADC1)-Pad40)") (class "Default")
      (node (ref "IC8") (pin "40") (pinfunction "PF1(ADC1)_40") (pintype "bidirectional"))
    )
    (net (code "96") (name "unconnected-(IC8-PF4(ADC4{slash}TCK)-Pad39)") (class "Default")
      (node (ref "IC8") (pin "39") (pinfunction "PF4(ADC4/TCK)_39") (pintype "bidirectional"))
    )
    (net (code "97") (name "unconnected-(IC8-PF5(ADC5{slash}TMS)-Pad38)") (class "Default")
      (node (ref "IC8") (pin "38") (pinfunction "PF5(ADC5/TMS)_38") (pintype "bidirectional"))
    )
    (net (code "98") (name "unconnected-(IC8-PF6(ADC6{slash}TDO)-Pad37)") (class "Default")
      (node (ref "IC8") (pin "37") (pinfunction "PF6(ADC6/TDO)_37") (pintype "bidirectional"))
    )
    (net (code "99") (name "unconnected-(IC8-PF7(ADC7(TDI)-Pad36)") (class "Default")
      (node (ref "IC8") (pin "36") (pinfunction "PF7(ADC7(TDI)_36") (pintype "bidirectional"))
    )
    (net (code "100") (name "unconnected-(JK1-PadRSH)") (class "Default")
      (node (ref "JK1") (pin "RSH") (pinfunction "RSH_RSH") (pintype "bidirectional"))
    )
    (net (code "101") (name "unconnected-(JK2-PadRSH)") (class "Default")
      (node (ref "JK2") (pin "RSH") (pinfunction "RSH_RSH") (pintype "bidirectional"))
    )
    (net (code "102") (name "unconnected-(JK3-PadRSH)") (class "Default")
      (node (ref "JK3") (pin "RSH") (pinfunction "RSH_RSH") (pintype "bidirectional"))
    )
  )
)
